# display-coln.net
KiCad netlist of a schematic drawn in EAGLE
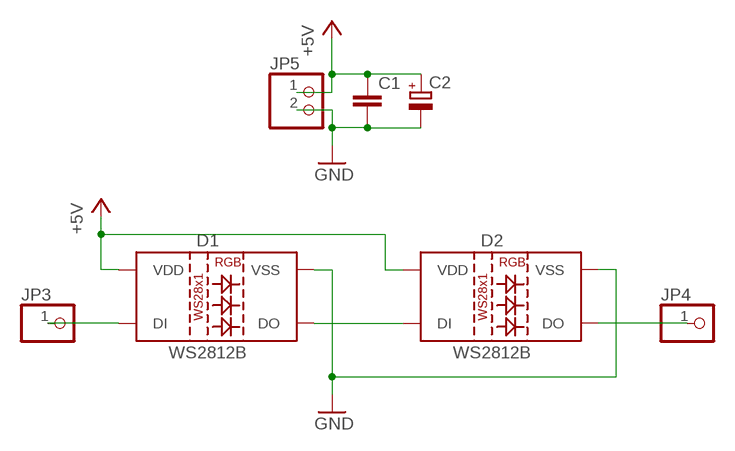
[diagram p0: schematic, sheet 1]

(export (version "E")
  (design (tool "Eeschema 10.0.6"))
  (components
    (comp (ref "C1")
      (value "C-EUC1206")
      (footprint "eagle-import:C1206")
      (libsource (lib "eagle-import") (part "C-EUC1206"))
    )
    (comp (ref "C2")
      (value "CPOL-EUE2.5-6")
      (footprint "eagle-import:E2,5-6")
      (libsource (lib "eagle-import") (part "CPOL-EUE2.5-6"))
    )
    (comp (ref "D1")
      (value "WS2812B")
      (footprint "eagle-import:WS2812B")
      (fields (field (name "MF") "Worldsemi"))
      (libsource (lib "eagle-import") (part "WS2812B"))
    )
    (comp (ref "D2")
      (value "WS2812B")
      (footprint "eagle-import:WS2812B")
      (fields (field (name "MF") "Worldsemi"))
      (libsource (lib "eagle-import") (part "WS2812B"))
    )
    (comp (ref "JP3")
      (value "PINHD-1X1")
      (footprint "eagle-import:1X01")
      (libsource (lib "eagle-import") (part "PINHD-1X1"))
    )
    (comp (ref "JP4")
      (value "PINHD-1X1")
      (footprint "eagle-import:1X01")
      (libsource (lib "eagle-import") (part "PINHD-1X1"))
    )
    (comp (ref "JP5")
      (value "PINHD-1X2")
      (footprint "eagle-import:1X02")
      (libsource (lib "eagle-import") (part "PINHD-1X2"))
    )
  )
  (nets
    (net (code "1") (name "+5V") (class "Default")
      (node (ref "C1") (pin "1") (pinfunction "1_1") (pintype "passive"))
      (node (ref "C2") (pin "+") (pinfunction "+_+") (pintype "passive"))
      (node (ref "D1") (pin "1") (pinfunction "VDD_1") (pintype "bidirectional"))
      (node (ref "D2") (pin "1") (pinfunction "VDD_1") (pintype "bidirectional"))
      (node (ref "JP5") (pin "1") (pinfunction "1_1") (pintype "passive"))
    )
    (net (code "2") (name "GND") (class "Default")
      (node (ref "C1") (pin "2") (pinfunction "2_2") (pintype "passive"))
      (node (ref "C2") (pin "-") (pinfunction "-_-") (pintype "passive"))
      (node (ref "D1") (pin "3") (pinfunction "VSS_3") (pintype "bidirectional"))
      (node (ref "D2") (pin "3") (pinfunction "VSS_3") (pintype "bidirectional"))
      (node (ref "JP5") (pin "2") (pinfunction "2_2") (pintype "passive"))
    )
    (net (code "3") (name "Net-(D1-DI)") (class "Default")
      (node (ref "D1") (pin "4") (pinfunction "DI_4") (pintype "bidirectional"))
      (node (ref "JP3") (pin "1") (pinfunction "1_1") (pintype "passive"))
    )
    (net (code "4") (name "Net-(D1-DO)") (class "Default")
      (node (ref "D1") (pin "2") (pinfunction "DO_2") (pintype "bidirectional"))
      (node (ref "D2") (pin "4") (pinfunction "DI_4") (pintype "bidirectional"))
    )
    (net (code "5") (name "Net-(D2-DO)") (class "Default")
      (node (ref "D2") (pin "2") (pinfunction "DO_2") (pintype "bidirectional"))
      (node (ref "JP4") (pin "1") (pinfunction "1_1") (pintype "passive"))
    )
  )
)
